# RF_2.net
KiCad netlist of a schematic drawn in EAGLE
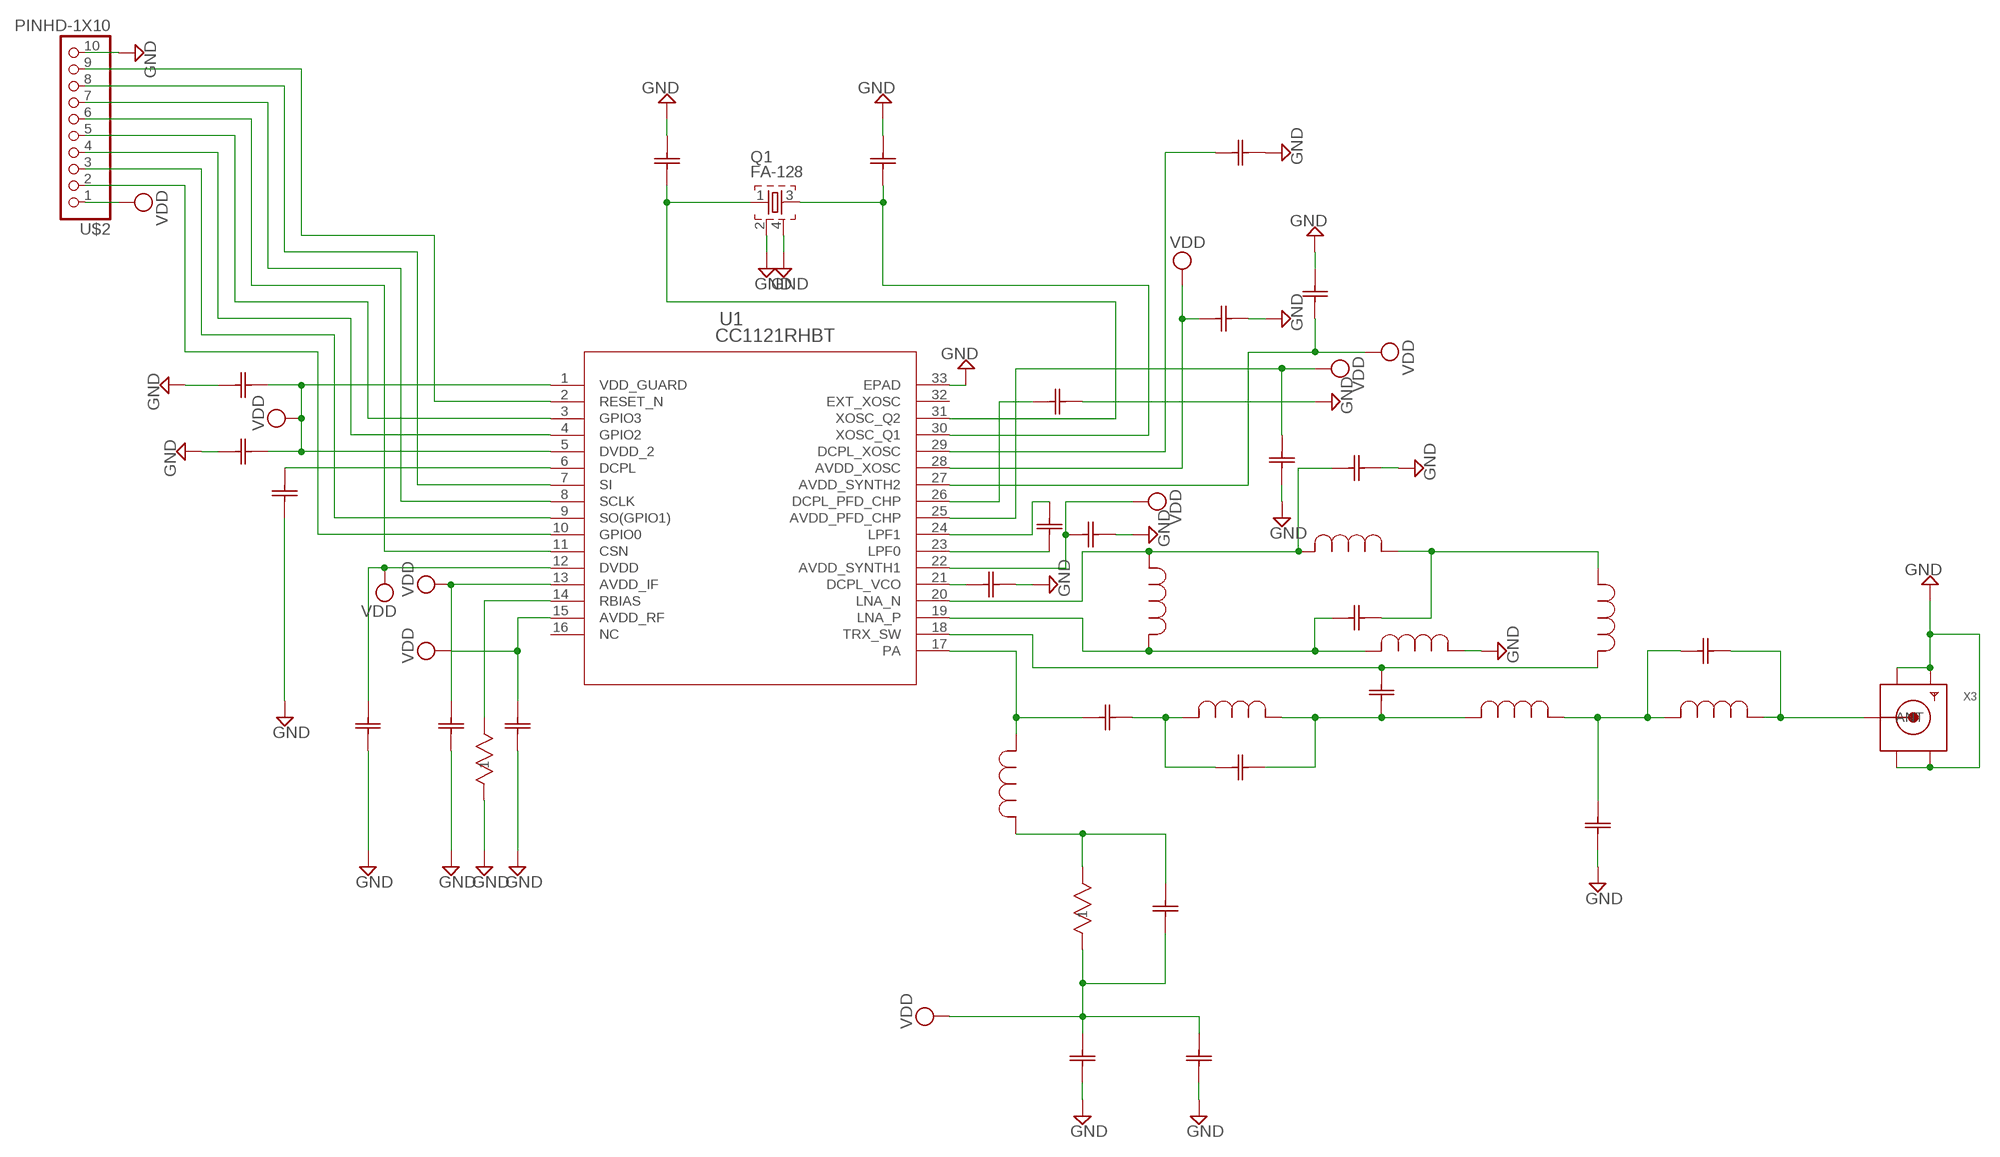
[diagram p0: schematic, sheet 1]

(export (version "E")
  (design (tool "Eeschema 10.0.6"))
  (components
    (comp (ref "C1")
      (value "220nF")
      (footprint "eagle-import:G-155_MUR")
      (fields
        (field (name "MANUFACTURER_PART_NUMBER") "GRM155R71A104KA01D")
        (field (name "COPYRIGHT") "Copyright (C) 2015 Accelerated Designs. All rights reserved")
      )
      (libsource (lib "eagle-import") (part "GRM155R71A104KA01D"))
    )
    (comp (ref "C2")
      (value "47nF")
      (footprint "eagle-import:G-155_MUR")
      (fields
        (field (name "MANUFACTURER_PART_NUMBER") "GRM155R71A104KA01D")
        (field (name "COPYRIGHT") "Copyright (C) 2015 Accelerated Designs. All rights reserved")
      )
      (libsource (lib "eagle-import") (part "GRM155R71A104KA01D"))
    )
    (comp (ref "C3")
      (value "15pF")
      (footprint "eagle-import:G-155_MUR")
      (fields
        (field (name "MANUFACTURER_PART_NUMBER") "GRM155R71A104KA01D")
        (field (name "COPYRIGHT") "Copyright (C) 2015 Accelerated Designs. All rights reserved")
      )
      (libsource (lib "eagle-import") (part "GRM155R71A104KA01D"))
    )
    (comp (ref "C4")
      (value "1pF")
      (footprint "eagle-import:G-155_MUR")
      (fields
        (field (name "MANUFACTURER_PART_NUMBER") "GRM155R71A104KA01D")
        (field (name "COPYRIGHT") "Copyright (C) 2015 Accelerated Designs. All rights reserved")
      )
      (libsource (lib "eagle-import") (part "GRM155R71A104KA01D"))
    )
    (comp (ref "C5")
      (value "2.2pF")
      (footprint "eagle-import:G-155_MUR")
      (fields
        (field (name "MANUFACTURER_PART_NUMBER") "GRM155R71A104KA01D")
        (field (name "COPYRIGHT") "Copyright (C) 2015 Accelerated Designs. All rights reserved")
      )
      (libsource (lib "eagle-import") (part "GRM155R71A104KA01D"))
    )
    (comp (ref "C6")
      (value "47nF")
      (footprint "eagle-import:G-155_MUR")
      (fields
        (field (name "MANUFACTURER_PART_NUMBER") "GRM155R71A104KA01D")
        (field (name "COPYRIGHT") "Copyright (C) 2015 Accelerated Designs. All rights reserved")
      )
      (libsource (lib "eagle-import") (part "GRM155R71A104KA01D"))
    )
    (comp (ref "C7")
      (value "47nF")
      (footprint "eagle-import:G-155_MUR")
      (fields
        (field (name "MANUFACTURER_PART_NUMBER") "GRM155R71A104KA01D")
        (field (name "COPYRIGHT") "Copyright (C) 2015 Accelerated Designs. All rights reserved")
      )
      (libsource (lib "eagle-import") (part "GRM155R71A104KA01D"))
    )
    (comp (ref "C8")
      (value "47nF")
      (footprint "eagle-import:G-155_MUR")
      (fields
        (field (name "MANUFACTURER_PART_NUMBER") "GRM155R71A104KA01D")
        (field (name "COPYRIGHT") "Copyright (C) 2015 Accelerated Designs. All rights reserved")
      )
      (libsource (lib "eagle-import") (part "GRM155R71A104KA01D"))
    )
    (comp (ref "C9")
      (value "220nF")
      (footprint "eagle-import:G-155_MUR")
      (fields
        (field (name "MANUFACTURER_PART_NUMBER") "GRM155R71A104KA01D")
        (field (name "COPYRIGHT") "Copyright (C) 2015 Accelerated Designs. All rights reserved")
      )
      (libsource (lib "eagle-import") (part "GRM155R71A104KA01D"))
    )
    (comp (ref "C10")
      (value "33pF")
      (footprint "eagle-import:G-155_MUR")
      (fields
        (field (name "MANUFACTURER_PART_NUMBER") "GRM155R71A104KA01D")
        (field (name "COPYRIGHT") "Copyright (C) 2015 Accelerated Designs. All rights reserved")
      )
      (libsource (lib "eagle-import") (part "GRM155R71A104KA01D"))
    )
    (comp (ref "C11")
      (value "10pF")
      (footprint "eagle-import:G-155_MUR")
      (fields
        (field (name "MANUFACTURER_PART_NUMBER") "GRM155R71A104KA01D")
        (field (name "COPYRIGHT") "Copyright (C) 2015 Accelerated Designs. All rights reserved")
      )
      (libsource (lib "eagle-import") (part "GRM155R71A104KA01D"))
    )
    (comp (ref "C12")
      (value "10pF")
      (footprint "eagle-import:G-155_MUR")
      (fields
        (field (name "MANUFACTURER_PART_NUMBER") "GRM155R71A104KA01D")
        (field (name "COPYRIGHT") "Copyright (C) 2015 Accelerated Designs. All rights reserved")
      )
      (libsource (lib "eagle-import") (part "GRM155R71A104KA01D"))
    )
    (comp (ref "C13")
      (value "3pF")
      (footprint "eagle-import:G-155_MUR")
      (fields
        (field (name "MANUFACTURER_PART_NUMBER") "GRM155R71A104KA01D")
        (field (name "COPYRIGHT") "Copyright (C) 2015 Accelerated Designs. All rights reserved")
      )
      (libsource (lib "eagle-import") (part "GRM155R71A104KA01D"))
    )
    (comp (ref "C14")
      (value "GRM155R71A104KA01D")
      (footprint "eagle-import:G-155_MUR")
      (fields (field (name "COPYRIGHT") "Copyright (C) 2015 Accelerated Designs. All rights reserved"))
      (libsource (lib "eagle-import") (part "GRM155R71A104KA01D"))
    )
    (comp (ref "C15")
      (value "3.3pF")
      (footprint "eagle-import:G-155_MUR")
      (fields
        (field (name "MANUFACTURER_PART_NUMBER") "GRM155R71A104KA01D")
        (field (name "COPYRIGHT") "Copyright (C) 2015 Accelerated Designs. All rights reserved")
      )
      (libsource (lib "eagle-import") (part "GRM155R71A104KA01D"))
    )
    (comp (ref "C16")
      (value "3.3pF")
      (footprint "eagle-import:G-155_MUR")
      (fields
        (field (name "MANUFACTURER_PART_NUMBER") "GRM155R71A104KA01D")
        (field (name "COPYRIGHT") "Copyright (C) 2015 Accelerated Designs. All rights reserved")
      )
      (libsource (lib "eagle-import") (part "GRM155R71A104KA01D"))
    )
    (comp (ref "C17")
      (value "10nF")
      (footprint "eagle-import:G-155_MUR")
      (fields
        (field (name "MANUFACTURER_PART_NUMBER") "GRM155R71A104KA01D")
        (field (name "COPYRIGHT") "Copyright (C) 2015 Accelerated Designs. All rights reserved")
      )
      (libsource (lib "eagle-import") (part "GRM155R71A104KA01D"))
    )
    (comp (ref "C18")
      (value "10nF")
      (footprint "eagle-import:G-155_MUR")
      (fields
        (field (name "MANUFACTURER_PART_NUMBER") "GRM155R71A104KA01D")
        (field (name "COPYRIGHT") "Copyright (C) 2015 Accelerated Designs. All rights reserved")
      )
      (libsource (lib "eagle-import") (part "GRM155R71A104KA01D"))
    )
    (comp (ref "C19")
      (value "1.8nF")
      (footprint "eagle-import:G-155_MUR")
      (fields
        (field (name "MANUFACTURER_PART_NUMBER") "GRM155R71A104KA01D")
        (field (name "COPYRIGHT") "Copyright (C) 2015 Accelerated Designs. All rights reserved")
      )
      (libsource (lib "eagle-import") (part "GRM155R71A104KA01D"))
    )
    (comp (ref "C20")
      (value "47nF")
      (footprint "eagle-import:G-155_MUR")
      (fields
        (field (name "MANUFACTURER_PART_NUMBER") "GRM155R71A104KA01D")
        (field (name "COPYRIGHT") "Copyright (C) 2015 Accelerated Designs. All rights reserved")
      )
      (libsource (lib "eagle-import") (part "GRM155R71A104KA01D"))
    )
    (comp (ref "C21")
      (value "47nF")
      (footprint "eagle-import:G-155_MUR")
      (fields
        (field (name "MANUFACTURER_PART_NUMBER") "GRM155R71A104KA01D")
        (field (name "COPYRIGHT") "Copyright (C) 2015 Accelerated Designs. All rights reserved")
      )
      (libsource (lib "eagle-import") (part "GRM155R71A104KA01D"))
    )
    (comp (ref "C22")
      (value "47nF")
      (footprint "eagle-import:G-155_MUR")
      (fields
        (field (name "MANUFACTURER_PART_NUMBER") "GRM155R71A104KA01D")
        (field (name "COPYRIGHT") "Copyright (C) 2015 Accelerated Designs. All rights reserved")
      )
      (libsource (lib "eagle-import") (part "GRM155R71A104KA01D"))
    )
    (comp (ref "C23")
      (value "47nF")
      (footprint "eagle-import:G-155_MUR")
      (fields
        (field (name "MANUFACTURER_PART_NUMBER") "GRM155R71A104KA01D")
        (field (name "COPYRIGHT") "Copyright (C) 2015 Accelerated Designs. All rights reserved")
      )
      (libsource (lib "eagle-import") (part "GRM155R71A104KA01D"))
    )
    (comp (ref "C24")
      (value "15pF")
      (footprint "eagle-import:G-155_MUR")
      (fields
        (field (name "MANUFACTURER_PART_NUMBER") "GRM155R71A104KA01D")
        (field (name "COPYRIGHT") "Copyright (C) 2015 Accelerated Designs. All rights reserved")
      )
      (libsource (lib "eagle-import") (part "GRM155R71A104KA01D"))
    )
    (comp (ref "C25")
      (value "15pF")
      (footprint "eagle-import:G-155_MUR")
      (fields
        (field (name "MANUFACTURER_PART_NUMBER") "GRM155R71A104KA01D")
        (field (name "COPYRIGHT") "Copyright (C) 2015 Accelerated Designs. All rights reserved")
      )
      (libsource (lib "eagle-import") (part "GRM155R71A104KA01D"))
    )
    (comp (ref "C26")
      (value "47nF")
      (footprint "eagle-import:G-155_MUR")
      (fields
        (field (name "MANUFACTURER_PART_NUMBER") "GRM155R71A104KA01D")
        (field (name "COPYRIGHT") "Copyright (C) 2015 Accelerated Designs. All rights reserved")
      )
      (libsource (lib "eagle-import") (part "GRM155R71A104KA01D"))
    )
    (comp (ref "L1")
      (value "10nH")
      (footprint "eagle-import:IND_LQW15AN13NG00D_MUR")
      (fields
        (field (name "MANUFACTURER_PART_NUMBER") "LQW15AN13NG00D")
        (field (name "COPYRIGHT") "Copyright (C) 2018 Accelerated Designs. All rights reserved")
      )
      (libsource (lib "eagle-import") (part "LQW15AN13NG00D"))
    )
    (comp (ref "L2")
      (value "10nH")
      (footprint "eagle-import:IND_LQW15AN13NG00D_MUR")
      (fields
        (field (name "MANUFACTURER_PART_NUMBER") "LQW15AN13NG00D")
        (field (name "COPYRIGHT") "Copyright (C) 2018 Accelerated Designs. All rights reserved")
      )
      (libsource (lib "eagle-import") (part "LQW15AN13NG00D"))
    )
    (comp (ref "L3")
      (value "10nH")
      (footprint "eagle-import:IND_LQW15AN13NG00D_MUR")
      (fields
        (field (name "MANUFACTURER_PART_NUMBER") "LQW15AN13NG00D")
        (field (name "COPYRIGHT") "Copyright (C) 2018 Accelerated Designs. All rights reserved")
      )
      (libsource (lib "eagle-import") (part "LQW15AN13NG00D"))
    )
    (comp (ref "L4")
      (value "12nH")
      (footprint "eagle-import:IND_LQW15AN13NG00D_MUR")
      (fields
        (field (name "MANUFACTURER_PART_NUMBER") "LQW15AN13NG00D")
        (field (name "COPYRIGHT") "Copyright (C) 2018 Accelerated Designs. All rights reserved")
      )
      (libsource (lib "eagle-import") (part "LQW15AN13NG00D"))
    )
    (comp (ref "L5")
      (value "15nH")
      (footprint "eagle-import:IND_LQW15AN13NG00D_MUR")
      (fields
        (field (name "MANUFACTURER_PART_NUMBER") "LQW15AN13NG00D")
        (field (name "COPYRIGHT") "Copyright (C) 2018 Accelerated Designs. All rights reserved")
      )
      (libsource (lib "eagle-import") (part "LQW15AN13NG00D"))
    )
    (comp (ref "L6")
      (value "12nH")
      (footprint "eagle-import:IND_LQW15AN13NG00D_MUR")
      (fields
        (field (name "MANUFACTURER_PART_NUMBER") "LQW15AN13NG00D")
        (field (name "COPYRIGHT") "Copyright (C) 2018 Accelerated Designs. All rights reserved")
      )
      (libsource (lib "eagle-import") (part "LQW15AN13NG00D"))
    )
    (comp (ref "L7")
      (value "12nH")
      (footprint "eagle-import:IND_LQW15AN13NG00D_MUR")
      (fields
        (field (name "MANUFACTURER_PART_NUMBER") "LQW15AN13NG00D")
        (field (name "COPYRIGHT") "Copyright (C) 2018 Accelerated Designs. All rights reserved")
      )
      (libsource (lib "eagle-import") (part "LQW15AN13NG00D"))
    )
    (comp (ref "L8")
      (value "12nH")
      (footprint "eagle-import:IND_LQW15AN13NG00D_MUR")
      (fields
        (field (name "MANUFACTURER_PART_NUMBER") "LQW15AN13NG00D")
        (field (name "COPYRIGHT") "Copyright (C) 2018 Accelerated Designs. All rights reserved")
      )
      (libsource (lib "eagle-import") (part "LQW15AN13NG00D"))
    )
    (comp (ref "Q1")
      (value "FA-128")
      (footprint "eagle-import:FA-128")
      (libsource (lib "eagle-import") (part "FA-128"))
    )
    (comp (ref "R1")
      (value "56k")
      (footprint "eagle-import:RES_1E0402_1XP5_KOA")
      (fields
        (field (name "MANUFACTURER_PART_NUMBER") "RK73H1ETTP1003F")
        (field (name "COPYRIGHT") "Copyright (C) 2018 Accelerated Designs. All rights reserved")
      )
      (libsource (lib "eagle-import") (part "RK73H1ETTP1003F"))
    )
    (comp (ref "R2")
      (value "56k")
      (footprint "eagle-import:RES_1E0402_1XP5_KOA")
      (fields
        (field (name "MANUFACTURER_PART_NUMBER") "RK73H1ETTP1003F")
        (field (name "COPYRIGHT") "Copyright (C) 2018 Accelerated Designs. All rights reserved")
      )
      (libsource (lib "eagle-import") (part "RK73H1ETTP1003F"))
    )
    (comp (ref "U$2")
      (value "PINHD-1X10")
      (footprint "eagle-import:1X10-BIG")
      (libsource (lib "eagle-import") (part "PINHD-1X10"))
    )
    (comp (ref "U1")
      (value "CC1121RHBT")
      (footprint "eagle-import:RHB32_3P45X3P45_TEX")
      (libsource (lib "eagle-import") (part "CC1121RHBT"))
    )
    (comp (ref "X3")
      (value "SMACONNECTOR_EDGE")
      (footprint "eagle-import:SMA_EDGELAUNCH")
      (libsource (lib "eagle-import") (part "SMACONNECTOR_EDGE"))
    )
  )
  (nets
    (net (code "1") (name "GND") (class "Default")
      (node (ref "C1") (pin "1") (pinfunction "1_1") (pintype "passive"))
      (node (ref "C11") (pin "1") (pinfunction "1_1") (pintype "passive"))
      (node (ref "C12") (pin "1") (pinfunction "1_1") (pintype "passive"))
      (node (ref "C13") (pin "1") (pinfunction "1_1") (pintype "passive"))
      (node (ref "C16") (pin "2") (pinfunction "2_2") (pintype "passive"))
      (node (ref "C17") (pin "2") (pinfunction "2_2") (pintype "passive"))
      (node (ref "C18") (pin "2") (pinfunction "2_2") (pintype "passive"))
      (node (ref "C2") (pin "1") (pinfunction "1_1") (pintype "passive"))
      (node (ref "C20") (pin "1") (pinfunction "1_1") (pintype "passive"))
      (node (ref "C21") (pin "2") (pinfunction "2_2") (pintype "passive"))
      (node (ref "C22") (pin "2") (pinfunction "2_2") (pintype "passive"))
      (node (ref "C23") (pin "2") (pinfunction "2_2") (pintype "passive"))
      (node (ref "C24") (pin "2") (pinfunction "2_2") (pintype "passive"))
      (node (ref "C25") (pin "2") (pinfunction "2_2") (pintype "passive"))
      (node (ref "C26") (pin "2") (pinfunction "2_2") (pintype "passive"))
      (node (ref "C6") (pin "1") (pinfunction "1_1") (pintype "passive"))
      (node (ref "C7") (pin "1") (pinfunction "1_1") (pintype "passive"))
      (node (ref "C8") (pin "1") (pinfunction "1_1") (pintype "passive"))
      (node (ref "C9") (pin "1") (pinfunction "1_1") (pintype "passive"))
      (node (ref "L8") (pin "1") (pinfunction "1_1") (pintype "passive"))
      (node (ref "Q1") (pin "2") (pinfunction "2_2") (pintype "passive"))
      (node (ref "Q1") (pin "4") (pinfunction "4_4") (pintype "passive"))
      (node (ref "R1") (pin "1") (pinfunction "1_1") (pintype "passive"))
      (node (ref "U$2") (pin "10") (pinfunction "10_10") (pintype "passive"))
      (node (ref "U1") (pin "33") (pinfunction "EPAD_33") (pintype "passive"))
      (node (ref "X3") (pin "GND@1") (pinfunction "GND4_GND@1") (pintype "power_in"))
      (node (ref "X3") (pin "GND@2") (pinfunction "GND3_GND@2") (pintype "power_in"))
      (node (ref "X3") (pin "GND@3") (pinfunction "GND2_GND@3") (pintype "power_in"))
      (node (ref "X3") (pin "GND@4") (pinfunction "GND1_GND@4") (pintype "power_in"))
    )
    (net (code "2") (name "Net-(C3-Pad2)") (class "Default")
      (node (ref "C3") (pin "2") (pinfunction "2_2") (pintype "passive"))
      (node (ref "C4") (pin "1") (pinfunction "1_1") (pintype "passive"))
      (node (ref "L2") (pin "2") (pinfunction "2_2") (pintype "passive"))
    )
    (net (code "3") (name "Net-(C4-Pad2)") (class "Default")
      (node (ref "C4") (pin "2") (pinfunction "2_2") (pintype "passive"))
      (node (ref "C5") (pin "1") (pinfunction "1_1") (pintype "passive"))
      (node (ref "L2") (pin "1") (pinfunction "1_1") (pintype "passive"))
      (node (ref "L3") (pin "2") (pinfunction "2_2") (pintype "passive"))
    )
    (net (code "4") (name "Net-(C10-Pad2)") (class "Default")
      (node (ref "C10") (pin "2") (pinfunction "2_2") (pintype "passive"))
      (node (ref "L1") (pin "2") (pinfunction "2_2") (pintype "passive"))
      (node (ref "R2") (pin "2") (pinfunction "2_2") (pintype "passive"))
    )
    (net (code "5") (name "Net-(C13-Pad2)") (class "Default")
      (node (ref "C13") (pin "2") (pinfunction "2_2") (pintype "passive"))
      (node (ref "C14") (pin "1") (pinfunction "1_1") (pintype "passive"))
      (node (ref "L3") (pin "1") (pinfunction "1_1") (pintype "passive"))
      (node (ref "L4") (pin "2") (pinfunction "2_2") (pintype "passive"))
    )
    (net (code "6") (name "Net-(C15-Pad2)") (class "Default")
      (node (ref "C15") (pin "2") (pinfunction "2_2") (pintype "passive"))
      (node (ref "L6") (pin "1") (pinfunction "1_1") (pintype "passive"))
      (node (ref "L7") (pin "2") (pinfunction "2_2") (pintype "passive"))
    )
    (net (code "7") (name "Net-(U1-CSN)") (class "Default")
      (node (ref "U$2") (pin "6") (pinfunction "6_6") (pintype "passive"))
      (node (ref "U1") (pin "11") (pinfunction "CSN_11") (pintype "input"))
    )
    (net (code "8") (name "Net-(U1-DCPL)") (class "Default")
      (node (ref "C9") (pin "2") (pinfunction "2_2") (pintype "passive"))
      (node (ref "U1") (pin "6") (pinfunction "DCPL_6") (pintype "power_in"))
    )
    (net (code "9") (name "Net-(U1-DCPL_PFD_CHP)") (class "Default")
      (node (ref "C21") (pin "1") (pinfunction "1_1") (pintype "passive"))
      (node (ref "U1") (pin "26") (pinfunction "DCPL_PFD_CHP_26") (pintype "power_in"))
    )
    (net (code "10") (name "Net-(U1-DCPL_VCO)") (class "Default")
      (node (ref "C17") (pin "1") (pinfunction "1_1") (pintype "passive"))
      (node (ref "U1") (pin "21") (pinfunction "DCPL_VCO_21") (pintype "power_in"))
    )
    (net (code "11") (name "Net-(U1-DCPL_XOSC)") (class "Default")
      (node (ref "C26") (pin "1") (pinfunction "1_1") (pintype "passive"))
      (node (ref "U1") (pin "29") (pinfunction "DCPL_XOSC_29") (pintype "power_in"))
    )
    (net (code "12") (name "Net-(U1-GPIO0)") (class "Default")
      (node (ref "U$2") (pin "2") (pinfunction "2_2") (pintype "passive"))
      (node (ref "U1") (pin "10") (pinfunction "GPIO0_10") (pintype "bidirectional"))
    )
    (net (code "13") (name "Net-(U1-GPIO2)") (class "Default")
      (node (ref "U$2") (pin "4") (pinfunction "4_4") (pintype "passive"))
      (node (ref "U1") (pin "4") (pinfunction "GPIO2_4") (pintype "bidirectional"))
    )
    (net (code "14") (name "Net-(U1-GPIO3)") (class "Default")
      (node (ref "U$2") (pin "5") (pinfunction "5_5") (pintype "passive"))
      (node (ref "U1") (pin "3") (pinfunction "GPIO3_3") (pintype "bidirectional"))
    )
    (net (code "15") (name "Net-(U1-LNA_N)") (class "Default")
      (node (ref "C16") (pin "1") (pinfunction "1_1") (pintype "passive"))
      (node (ref "L5") (pin "2") (pinfunction "2_2") (pintype "passive"))
      (node (ref "L6") (pin "2") (pinfunction "2_2") (pintype "passive"))
      (node (ref "U1") (pin "20") (pinfunction "LNA_N_20") (pintype "passive"))
    )
    (net (code "16") (name "Net-(U1-LNA_P)") (class "Default")
      (node (ref "C15") (pin "1") (pinfunction "1_1") (pintype "passive"))
      (node (ref "L5") (pin "1") (pinfunction "1_1") (pintype "passive"))
      (node (ref "L8") (pin "2") (pinfunction "2_2") (pintype "passive"))
      (node (ref "U1") (pin "19") (pinfunction "LNA_P_19") (pintype "passive"))
    )
    (net (code "17") (name "Net-(U1-LPF0)") (class "Default")
      (node (ref "C19") (pin "1") (pinfunction "1_1") (pintype "passive"))
      (node (ref "U1") (pin "23") (pinfunction "LPF0_23") (pintype "passive"))
    )
    (net (code "18") (name "Net-(U1-LPF1)") (class "Default")
      (node (ref "C19") (pin "2") (pinfunction "2_2") (pintype "passive"))
      (node (ref "U1") (pin "24") (pinfunction "LPF1_24") (pintype "passive"))
    )
    (net (code "19") (name "Net-(U1-PA)") (class "Default")
      (node (ref "C3") (pin "1") (pinfunction "1_1") (pintype "passive"))
      (node (ref "L1") (pin "1") (pinfunction "1_1") (pintype "passive"))
      (node (ref "U1") (pin "17") (pinfunction "PA_17") (pintype "passive"))
    )
    (net (code "20") (name "Net-(U1-RBIAS)") (class "Default")
      (node (ref "R1") (pin "2") (pinfunction "2_2") (pintype "passive"))
      (node (ref "U1") (pin "14") (pinfunction "RBIAS_14") (pintype "passive"))
    )
    (net (code "21") (name "Net-(U1-RESET_N)") (class "Default")
      (node (ref "U$2") (pin "9") (pinfunction "9_9") (pintype "passive"))
      (node (ref "U1") (pin "2") (pinfunction "RESET_N_2") (pintype "input"))
    )
    (net (code "22") (name "Net-(U1-SCLK)") (class "Default")
      (node (ref "U$2") (pin "7") (pinfunction "7_7") (pintype "passive"))
      (node (ref "U1") (pin "8") (pinfunction "SCLK_8") (pintype "input"))
    )
    (net (code "23") (name "Net-(U1-SI)") (class "Default")
      (node (ref "U$2") (pin "8") (pinfunction "8_8") (pintype "passive"))
      (node (ref "U1") (pin "7") (pinfunction "SI_7") (pintype "input"))
    )
    (net (code "24") (name "Net-(U1-SO(GPIO1))") (class "Default")
      (node (ref "U$2") (pin "3") (pinfunction "3_3") (pintype "passive"))
      (node (ref "U1") (pin "9") (pinfunction "SO(GPIO1)_9") (pintype "bidirectional"))
    )
    (net (code "25") (name "Net-(U1-TRX_SW)") (class "Default")
      (node (ref "C5") (pin "2") (pinfunction "2_2") (pintype "passive"))
      (node (ref "L7") (pin "1") (pinfunction "1_1") (pintype "passive"))
      (node (ref "U1") (pin "18") (pinfunction "TRX_SW_18") (pintype "passive"))
    )
    (net (code "26") (name "Net-(U1-XOSC_Q1)") (class "Default")
      (node (ref "C25") (pin "1") (pinfunction "1_1") (pintype "passive"))
      (node (ref "Q1") (pin "3") (pinfunction "3_3") (pintype "passive"))
      (node (ref "U1") (pin "30") (pinfunction "XOSC_Q1_30") (pintype "passive"))
    )
    (net (code "27") (name "Net-(U1-XOSC_Q2)") (class "Default")
      (node (ref "C24") (pin "1") (pinfunction "1_1") (pintype "passive"))
      (node (ref "Q1") (pin "1") (pinfunction "1_1") (pintype "passive"))
      (node (ref "U1") (pin "31") (pinfunction "XOSC_Q2_31") (pintype "passive"))
    )
    (net (code "28") (name "Net-(X3-ANT)") (class "Default")
      (node (ref "C14") (pin "2") (pinfunction "2_2") (pintype "passive"))
      (node (ref "L4") (pin "1") (pinfunction "1_1") (pintype "passive"))
      (node (ref "X3") (pin "P") (pinfunction "ANT_P") (pintype "bidirectional"))
    )
    (net (code "29") (name "VDD") (class "Default")
      (node (ref "C1") (pin "2") (pinfunction "2_2") (pintype "passive"))
      (node (ref "C10") (pin "1") (pinfunction "1_1") (pintype "passive"))
      (node (ref "C11") (pin "2") (pinfunction "2_2") (pintype "passive"))
      (node (ref "C12") (pin "2") (pinfunction "2_2") (pintype "passive"))
      (node (ref "C18") (pin "1") (pinfunction "1_1") (pintype "passive"))
      (node (ref "C2") (pin "2") (pinfunction "2_2") (pintype "passive"))
      (node (ref "C20") (pin "2") (pinfunction "2_2") (pintype "passive"))
      (node (ref "C22") (pin "1") (pinfunction "1_1") (pintype "passive"))
      (node (ref "C23") (pin "1") (pinfunction "1_1") (pintype "passive"))
      (node (ref "C6") (pin "2") (pinfunction "2_2") (pintype "passive"))
      (node (ref "C7") (pin "2") (pinfunction "2_2") (pintype "passive"))
      (node (ref "C8") (pin "2") (pinfunction "2_2") (pintype "passive"))
      (node (ref "R2") (pin "1") (pinfunction "1_1") (pintype "passive"))
      (node (ref "U$2") (pin "1") (pinfunction "1_1") (pintype "passive"))
      (node (ref "U1") (pin "1") (pinfunction "VDD_GUARD_1") (pintype "power_in"))
      (node (ref "U1") (pin "12") (pinfunction "DVDD_12") (pintype "power_in"))
      (node (ref "U1") (pin "13") (pinfunction "AVDD_IF_13") (pintype "power_in"))
      (node (ref "U1") (pin "15") (pinfunction "AVDD_RF_15") (pintype "power_in"))
      (node (ref "U1") (pin "22") (pinfunction "AVDD_SYNTH1_22") (pintype "power_in"))
      (node (ref "U1") (pin "25") (pinfunction "AVDD_PFD_CHP_25") (pintype "power_in"))
      (node (ref "U1") (pin "27") (pinfunction "AVDD_SYNTH2_27") (pintype "power_in"))
      (node (ref "U1") (pin "28") (pinfunction "AVDD_XOSC_28") (pintype "power_in"))
      (node (ref "U1") (pin "5") (pinfunction "DVDD_2_5") (pintype "power_in"))
    )
    (net (code "30") (name "unconnected-(U1-EXT_XOSC-Pad32)") (class "Default")
      (node (ref "U1") (pin "32") (pinfunction "EXT_XOSC_32") (pintype "input"))
    )
    (net (code "31") (name "unconnected-(U1-NC-Pad16)") (class "Default")
      (node (ref "U1") (pin "16") (pinfunction "NC_16") (pintype "no_connect"))
    )
  )
)
